# comparator.net
KiCad netlist of a schematic drawn in EAGLE
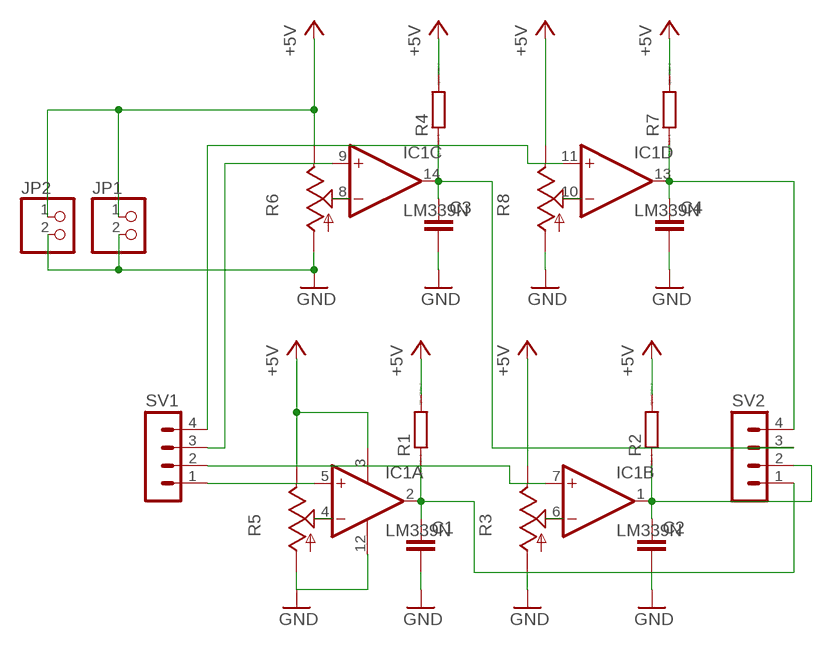
[diagram p0: schematic, sheet 1]

(export (version "E")
  (design (tool "Eeschema 10.0.6"))
  (components
    (comp (ref "C1")
      (value "C-EU075-032X103")
      (footprint "eagle-import:C075-032X103")
      (libsource (lib "eagle-import") (part "C-EU075-032X103"))
    )
    (comp (ref "C2")
      (value "C-EU075-032X103")
      (footprint "eagle-import:C075-032X103")
      (libsource (lib "eagle-import") (part "C-EU075-032X103"))
    )
    (comp (ref "C3")
      (value "C-EU075-032X103")
      (footprint "eagle-import:C075-032X103")
      (libsource (lib "eagle-import") (part "C-EU075-032X103"))
    )
    (comp (ref "C4")
      (value "C-EU075-032X103")
      (footprint "eagle-import:C075-032X103")
      (libsource (lib "eagle-import") (part "C-EU075-032X103"))
    )
    (comp (ref "IC1")
      (value "LM339N")
      (footprint "eagle-import:DIL14")
      (libsource (lib "eagle-import") (part "LM339N"))
    )
    (comp (ref "JP1")
      (value "PINHD-1X2")
      (footprint "eagle-import:1X02")
      (libsource (lib "eagle-import") (part "PINHD-1X2"))
    )
    (comp (ref "JP2")
      (value "PINHD-1X2")
      (footprint "eagle-import:1X02")
      (libsource (lib "eagle-import") (part "PINHD-1X2"))
    )
    (comp (ref "R1")
      (value "R0207/10")
      (footprint "eagle-import:0207_10")
      (libsource (lib "eagle-import") (part "R0207/10"))
    )
    (comp (ref "R2")
      (value "R0207/10")
      (footprint "eagle-import:0207_10")
      (libsource (lib "eagle-import") (part "R0207/10"))
    )
    (comp (ref "R3")
      (value "TRIM_US-RS3")
      (footprint "eagle-import:RS3")
      (libsource (lib "eagle-import") (part "TRIM_US-RS3"))
    )
    (comp (ref "R4")
      (value "R0207/10")
      (footprint "eagle-import:0207_10")
      (libsource (lib "eagle-import") (part "R0207/10"))
    )
    (comp (ref "R5")
      (value "TRIM_US-RS3")
      (footprint "eagle-import:RS3")
      (libsource (lib "eagle-import") (part "TRIM_US-RS3"))
    )
    (comp (ref "R6")
      (value "TRIM_US-RS3")
      (footprint "eagle-import:RS3")
      (libsource (lib "eagle-import") (part "TRIM_US-RS3"))
    )
    (comp (ref "R7")
      (value "R0207/10")
      (footprint "eagle-import:0207_10")
      (libsource (lib "eagle-import") (part "R0207/10"))
    )
    (comp (ref "R8")
      (value "TRIM_US-RS3")
      (footprint "eagle-import:RS3")
      (libsource (lib "eagle-import") (part "TRIM_US-RS3"))
    )
    (comp (ref "SV1")
      (value "MA04-1")
      (footprint "eagle-import:MA04-1")
      (libsource (lib "eagle-import") (part "MA04-1"))
    )
    (comp (ref "SV2")
      (value "MA04-1")
      (footprint "eagle-import:MA04-1")
      (libsource (lib "eagle-import") (part "MA04-1"))
    )
  )
  (nets
    (net (code "1") (name "+5V") (class "Default")
      (node (ref "IC1") (pin "3") (pinfunction "V+_3") (pintype "power_in"))
      (node (ref "JP1") (pin "1") (pinfunction "1_1") (pintype "passive"))
      (node (ref "JP2") (pin "1") (pinfunction "1_1") (pintype "passive"))
      (node (ref "R1") (pin "2") (pinfunction "2_2") (pintype "passive"))
      (node (ref "R2") (pin "2") (pinfunction "2_2") (pintype "passive"))
      (node (ref "R3") (pin "E") (pinfunction "E_E") (pintype "passive"))
      (node (ref "R4") (pin "2") (pinfunction "2_2") (pintype "passive"))
      (node (ref "R5") (pin "E") (pinfunction "E_E") (pintype "passive"))
      (node (ref "R6") (pin "E") (pinfunction "E_E") (pintype "passive"))
      (node (ref "R7") (pin "2") (pinfunction "2_2") (pintype "passive"))
      (node (ref "R8") (pin "E") (pinfunction "E_E") (pintype "passive"))
    )
    (net (code "2") (name "GND") (class "Default")
      (node (ref "C1") (pin "2") (pinfunction "2_2") (pintype "passive"))
      (node (ref "C2") (pin "2") (pinfunction "2_2") (pintype "passive"))
      (node (ref "C3") (pin "2") (pinfunction "2_2") (pintype "passive"))
      (node (ref "C4") (pin "2") (pinfunction "2_2") (pintype "passive"))
      (node (ref "IC1") (pin "12") (pinfunction "GND_12") (pintype "power_in"))
      (node (ref "JP1") (pin "2") (pinfunction "2_2") (pintype "passive"))
      (node (ref "JP2") (pin "2") (pinfunction "2_2") (pintype "passive"))
      (node (ref "R3") (pin "A") (pinfunction "A_A") (pintype "passive"))
      (node (ref "R5") (pin "A") (pinfunction "A_A") (pintype "passive"))
      (node (ref "R6") (pin "A") (pinfunction "A_A") (pintype "passive"))
      (node (ref "R8") (pin "A") (pinfunction "A_A") (pintype "passive"))
    )
    (net (code "3") (name "Net-(IC1A-+IN)") (class "Default")
      (node (ref "IC1") (pin "5") (pinfunction "+IN_5") (pintype "input"))
      (node (ref "SV1") (pin "1") (pinfunction "1_1") (pintype "passive"))
    )
    (net (code "4") (name "Net-(IC1A--IN)") (class "Default")
      (node (ref "IC1") (pin "4") (pinfunction "-IN_4") (pintype "input"))
      (node (ref "R5") (pin "S") (pinfunction "S_S") (pintype "passive"))
    )
    (net (code "5") (name "Net-(IC1A-OUT)") (class "Default")
      (node (ref "C1") (pin "1") (pinfunction "1_1") (pintype "passive"))
      (node (ref "IC1") (pin "2") (pinfunction "OUT_2") (pintype "open_collector"))
      (node (ref "R1") (pin "1") (pinfunction "1_1") (pintype "passive"))
      (node (ref "SV2") (pin "1") (pinfunction "1_1") (pintype "passive"))
    )
    (net (code "6") (name "Net-(IC1B-+IN)") (class "Default")
      (node (ref "IC1") (pin "7") (pinfunction "+IN_7") (pintype "input"))
      (node (ref "SV1") (pin "2") (pinfunction "2_2") (pintype "passive"))
    )
    (net (code "7") (name "Net-(IC1B--IN)") (class "Default")
      (node (ref "IC1") (pin "6") (pinfunction "-IN_6") (pintype "input"))
      (node (ref "R3") (pin "S") (pinfunction "S_S") (pintype "passive"))
    )
    (net (code "8") (name "Net-(IC1B-OUT)") (class "Default")
      (node (ref "C2") (pin "1") (pinfunction "1_1") (pintype "passive"))
      (node (ref "IC1") (pin "1") (pinfunction "OUT_1") (pintype "open_collector"))
      (node (ref "R2") (pin "1") (pinfunction "1_1") (pintype "passive"))
      (node (ref "SV2") (pin "2") (pinfunction "2_2") (pintype "passive"))
    )
    (net (code "9") (name "Net-(IC1C-+IN)") (class "Default")
      (node (ref "IC1") (pin "9") (pinfunction "+IN_9") (pintype "input"))
      (node (ref "SV1") (pin "3") (pinfunction "3_3") (pintype "passive"))
    )
    (net (code "10") (name "Net-(IC1C--IN)") (class "Default")
      (node (ref "IC1") (pin "8") (pinfunction "-IN_8") (pintype "input"))
      (node (ref "R6") (pin "S") (pinfunction "S_S") (pintype "passive"))
    )
    (net (code "11") (name "Net-(IC1C-OUT)") (class "Default")
      (node (ref "C3") (pin "1") (pinfunction "1_1") (pintype "passive"))
      (node (ref "IC1") (pin "14") (pinfunction "OUT_14") (pintype "open_collector"))
      (node (ref "R4") (pin "1") (pinfunction "1_1") (pintype "passive"))
      (node (ref "SV2") (pin "3") (pinfunction "3_3") (pintype "passive"))
    )
    (net (code "12") (name "Net-(IC1D-+IN)") (class "Default")
      (node (ref "IC1") (pin "11") (pinfunction "+IN_11") (pintype "input"))
      (node (ref "SV1") (pin "4") (pinfunction "4_4") (pintype "passive"))
    )
    (net (code "13") (name "Net-(IC1D--IN)") (class "Default")
      (node (ref "IC1") (pin "10") (pinfunction "-IN_10") (pintype "input"))
      (node (ref "R8") (pin "S") (pinfunction "S_S") (pintype "passive"))
    )
    (net (code "14") (name "Net-(IC1D-OUT)") (class "Default")
      (node (ref "C4") (pin "1") (pinfunction "1_1") (pintype "passive"))
      (node (ref "IC1") (pin "13") (pinfunction "OUT_13") (pintype "open_collector"))
      (node (ref "R7") (pin "1") (pinfunction "1_1") (pintype "passive"))
      (node (ref "SV2") (pin "4") (pinfunction "4_4") (pintype "passive"))
    )
  )
)
